# uart.net
KiCad netlist of a schematic drawn in Altium Designer
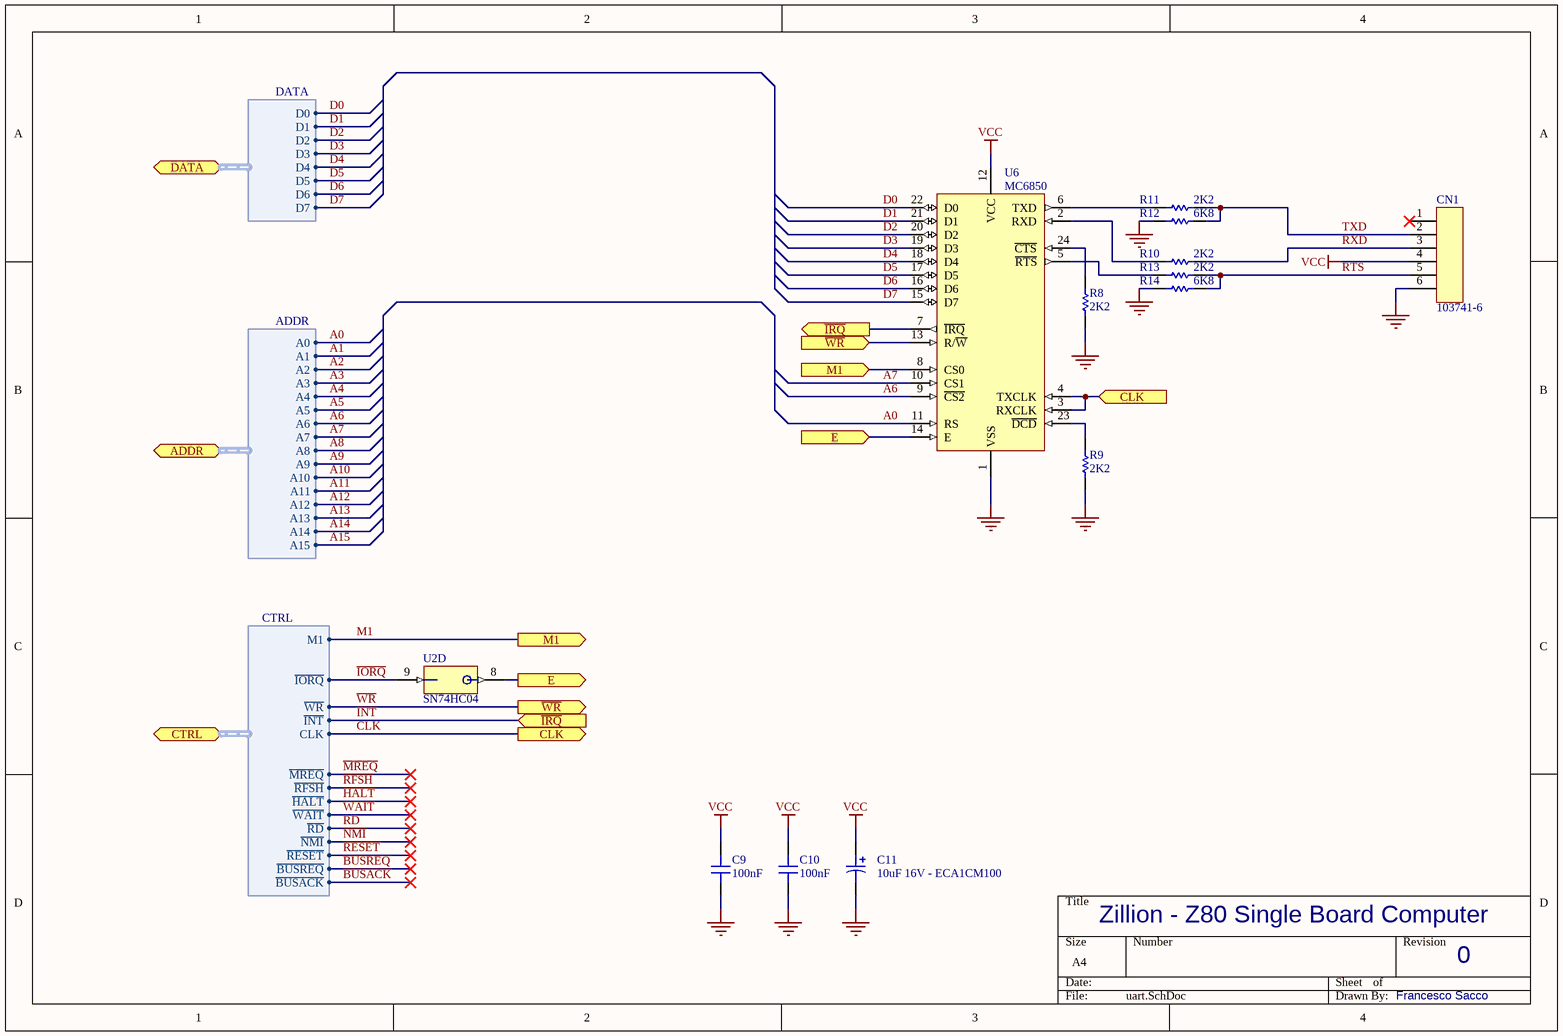
[diagram p0: uart.SchDoc]

(export (version "E")
  (design (tool "Eeschema 10.0.6"))
  (components
    (comp (ref "C9")
      (value "100nF")
      (footprint "DiskCapacitor")
      (description "Capacitor")
      (libsource (lib "Basic") (part "Capacitor"))
    )
    (comp (ref "C10")
      (value "100nF")
      (footprint "DiskCapacitor")
      (description "Capacitor")
      (libsource (lib "Basic") (part "Capacitor"))
    )
    (comp (ref "C11")
      (value "10uF 16V - ECA1CM100")
      (footprint "ECA 5x11")
      (description "10uF 16V")
      (libsource (lib "Panasonic") (part "ECA1CM100"))
    )
    (comp (ref "CN1")
      (value "103741-6")
      (footprint "103741-6")
      (description "CONN Breakaway Single Row")
      (libsource (lib "TE Connectivity") (part "103741-6"))
    )
    (comp (ref "R8") (value "2K2") (footprint "CR12") (libsource (lib "Basic") (part "Resistor")))
    (comp (ref "R9") (value "2K2") (footprint "CR12") (libsource (lib "Basic") (part "Resistor")))
    (comp (ref "R10") (value "2K2") (footprint "CR12") (libsource (lib "Basic") (part "Resistor")))
    (comp (ref "R11") (value "2K2") (footprint "CR12") (libsource (lib "Basic") (part "Resistor")))
    (comp (ref "R12") (value "6K8") (footprint "CR12") (libsource (lib "Basic") (part "Resistor")))
    (comp (ref "R13") (value "2K2") (footprint "CR12") (libsource (lib "Basic") (part "Resistor")))
    (comp (ref "R14") (value "6K8") (footprint "CR12") (libsource (lib "Basic") (part "Resistor")))
    (comp (ref "U2")
      (value "SN74HC04")
      (footprint "TSSOP14")
      (description "Hex Inverters")
      (libsource (lib "Texas Instruments") (part "SN74HC04"))
    )
    (comp (ref "U6")
      (value "MC6850")
      (footprint "PDIP24")
      (description "Asynchronous Communications Interface Adapter (ACIA)")
      (libsource (lib "Motorola") (part "MC6850"))
    )
  )
  (nets
    (net (code "4") (name "/A0") (class "Default")
      (node (ref "U6") (pin "11") (pinfunction "RS_11") (pintype "input"))
    )
    (net (code "10") (name "/A6") (class "Default")
      (node (ref "U6") (pin "9") (pinfunction "~{CS2}_9") (pintype "input"))
    )
    (net (code "11") (name "/A7") (class "Default")
      (node (ref "U6") (pin "10") (pinfunction "CS1_10") (pintype "input"))
    )
    (net (code "20") (name "/CLK") (class "Default")
      (node (ref "U6") (pin "3") (pinfunction "RXCLK_3") (pintype "input"))
      (node (ref "U6") (pin "4") (pinfunction "TXCLK_4") (pintype "input"))
    )
    (net (code "21") (name "/D0") (class "Default")
      (node (ref "U6") (pin "22") (pinfunction "D0_22") (pintype "bidirectional"))
    )
    (net (code "22") (name "/D1") (class "Default")
      (node (ref "U6") (pin "21") (pinfunction "D1_21") (pintype "bidirectional"))
    )
    (net (code "23") (name "/D2") (class "Default")
      (node (ref "U6") (pin "20") (pinfunction "D2_20") (pintype "bidirectional"))
    )
    (net (code "24") (name "/D3") (class "Default")
      (node (ref "U6") (pin "19") (pinfunction "D3_19") (pintype "bidirectional"))
    )
    (net (code "25") (name "/D4") (class "Default")
      (node (ref "U6") (pin "18") (pinfunction "D4_18") (pintype "bidirectional"))
    )
    (net (code "26") (name "/D5") (class "Default")
      (node (ref "U6") (pin "17") (pinfunction "D5_17") (pintype "bidirectional"))
    )
    (net (code "27") (name "/D6") (class "Default")
      (node (ref "U6") (pin "16") (pinfunction "D6_16") (pintype "bidirectional"))
    )
    (net (code "28") (name "/D7") (class "Default")
      (node (ref "U6") (pin "15") (pinfunction "D7_15") (pintype "bidirectional"))
    )
    (net (code "29") (name "/E") (class "Default")
      (node (ref "U2") (pin "8") (pinfunction "Y_8") (pintype "output"))
      (node (ref "U6") (pin "14") (pinfunction "E_14") (pintype "input"))
    )
    (net (code "30") (name "/M1") (class "Default")
      (node (ref "U6") (pin "8") (pinfunction "CS0_8") (pintype "input"))
    )
    (net (code "31") (name "/RTS") (class "Default")
      (node (ref "CN1") (pin "5") (pinfunction "5_5") (pintype "passive"))
      (node (ref "R13") (pin "1") (pinfunction "1_1") (pintype "passive"))
      (node (ref "R14") (pin "2") (pinfunction "2_2") (pintype "passive"))
    )
    (net (code "32") (name "/RXD") (class "Default")
      (node (ref "CN1") (pin "3") (pinfunction "3_3") (pintype "passive"))
      (node (ref "R10") (pin "1") (pinfunction "1_1") (pintype "passive"))
    )
    (net (code "33") (name "/TXD") (class "Default")
      (node (ref "CN1") (pin "2") (pinfunction "2_2") (pintype "passive"))
      (node (ref "R11") (pin "1") (pinfunction "1_1") (pintype "passive"))
      (node (ref "R12") (pin "2") (pinfunction "2_2") (pintype "passive"))
    )
    (net (code "40") (name "/~{INT}") (class "Default")
      (node (ref "U6") (pin "7") (pinfunction "~{IRQ}_7") (pintype "output"))
    )
    (net (code "41") (name "/~{IORQ}") (class "Default")
      (node (ref "U2") (pin "9") (pinfunction "A_9") (pintype "input"))
    )
    (net (code "48") (name "/~{WR}") (class "Default")
      (node (ref "U6") (pin "13") (pinfunction "R/~{W}_13") (pintype "input"))
    )
    (net (code "49") (name "GND") (class "Default")
      (node (ref "C10") (pin "1") (pinfunction "1_1") (pintype "passive"))
      (node (ref "C11") (pin "2") (pinfunction "2_2") (pintype "passive"))
      (node (ref "C9") (pin "1") (pinfunction "1_1") (pintype "passive"))
      (node (ref "CN1") (pin "6") (pinfunction "6_6") (pintype "passive"))
      (node (ref "R12") (pin "1") (pinfunction "1_1") (pintype "passive"))
      (node (ref "R14") (pin "1") (pinfunction "1_1") (pintype "passive"))
      (node (ref "R8") (pin "1") (pinfunction "1_1") (pintype "passive"))
      (node (ref "R9") (pin "1") (pinfunction "1_1") (pintype "passive"))
      (node (ref "U6") (pin "1") (pinfunction "VSS_1") (pintype "power_in"))
    )
    (net (code "50") (name "Net-(U6-RXD)") (class "Default")
      (node (ref "R10") (pin "2") (pinfunction "2_2") (pintype "passive"))
      (node (ref "U6") (pin "2") (pinfunction "RXD_2") (pintype "input"))
    )
    (net (code "51") (name "Net-(U6-TXD)") (class "Default")
      (node (ref "R11") (pin "2") (pinfunction "2_2") (pintype "passive"))
      (node (ref "U6") (pin "6") (pinfunction "TXD_6") (pintype "output"))
    )
    (net (code "52") (name "Net-(U6-~{CTS})") (class "Default")
      (node (ref "R8") (pin "2") (pinfunction "2_2") (pintype "passive"))
      (node (ref "U6") (pin "24") (pinfunction "~{CTS}_24") (pintype "input"))
    )
    (net (code "53") (name "Net-(U6-~{DCD})") (class "Default")
      (node (ref "R9") (pin "2") (pinfunction "2_2") (pintype "passive"))
      (node (ref "U6") (pin "23") (pinfunction "~{DCD}_23") (pintype "input"))
    )
    (net (code "54") (name "Net-(U6-~{RTS})") (class "Default")
      (node (ref "R13") (pin "2") (pinfunction "2_2") (pintype "passive"))
      (node (ref "U6") (pin "5") (pinfunction "~{RTS}_5") (pintype "output"))
    )
    (net (code "55") (name "VCC") (class "Default")
      (node (ref "C10") (pin "2") (pinfunction "2_2") (pintype "passive"))
      (node (ref "C11") (pin "1") (pinfunction "1_1") (pintype "passive"))
      (node (ref "C9") (pin "2") (pinfunction "2_2") (pintype "passive"))
      (node (ref "CN1") (pin "4") (pinfunction "4_4") (pintype "passive"))
      (node (ref "U6") (pin "12") (pinfunction "VCC_12") (pintype "power_in"))
    )
    (net (code "56") (name "unconnected-(CN1-Pad1)") (class "Default")
      (node (ref "CN1") (pin "1") (pinfunction "1_1") (pintype "passive+no_connect"))
    )
  )
)
